# CAS_4.net
KiCad netlist of a schematic drawn in Altium Designer
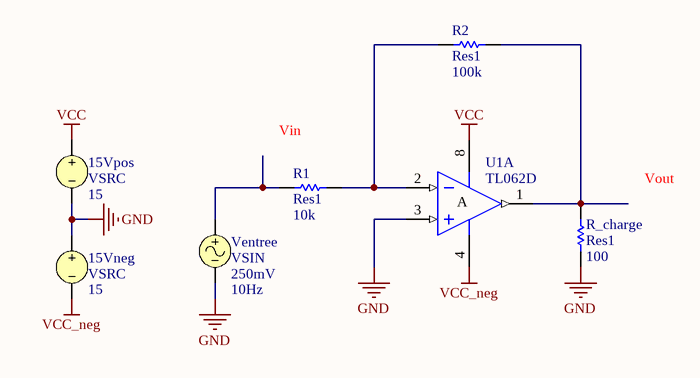
[diagram p0: CAS_4.SchDoc]

(export (version "E")
  (design (tool "Eeschema 10.0.6"))
  (components
    (comp (ref "15Vneg")
      (value "VSRC")
      (description "Voltage Source")
      (fields (field (name "ALTIUM_VALUE") "15") (field (name "PUBLISHER") "Altium Limited"))
      (libsource (lib "Simulation Generic Components") (part "VSRC"))
    )
    (comp (ref "15Vpos")
      (value "VSRC")
      (description "Voltage Source")
      (fields (field (name "ALTIUM_VALUE") "15") (field (name "PUBLISHER") "Altium Limited"))
      (libsource (lib "Simulation Generic Components") (part "VSRC"))
    )
    (comp (ref "R1")
      (value "Res1")
      (footprint "AXIAL-0.3")
      (description "Resistor")
      (fields (field (name "ALTIUM_VALUE") "10k") (field (name "PUBLISHER") "Altium Limited"))
      (libsource (lib "Miscellaneous Devices") (part "Res1"))
    )
    (comp (ref "R2")
      (value "Res1")
      (footprint "AXIAL-0.3")
      (description "Resistor")
      (fields (field (name "ALTIUM_VALUE") "100k") (field (name "PUBLISHER") "Altium Limited"))
      (libsource (lib "Miscellaneous Devices") (part "Res1"))
    )
    (comp (ref "R_charge")
      (value "Res1")
      (footprint "AXIAL-0.3")
      (description "Resistor")
      (fields (field (name "ALTIUM_VALUE") "100") (field (name "PUBLISHER") "Altium Limited"))
      (libsource (lib "Miscellaneous Devices") (part "Res1"))
    )
    (comp (ref "U1")
      (value "TL062D")
      (footprint "D008_L")
      (description "Low-Power JFET-Input Operational Amplifier")
      (fields (field (name "PUBLISHER") "Altium Limited"))
      (libsource (lib "TI Operational Amplifier") (part "TL062D"))
    )
    (comp (ref "Ventree")
      (value "VSIN")
      (description "Sinusoidal Voltage Source")
      (fields
        (field (name "AMPLITUDE") "250mV")
        (field (name "FREQUENCY") "10Hz")
        (field (name "PUBLISHER") "Altium Limited")
      )
      (libsource (lib "Simulation Sources") (part "VSIN"))
    )
  )
  (nets
    (net (code "1") (name "GND") (class "Default")
      (node (ref "15Vneg") (pin "1") (pinfunction "1_1") (pintype "passive"))
      (node (ref "15Vpos") (pin "2") (pinfunction "2_2") (pintype "passive"))
      (node (ref "R_charge") (pin "1") (pinfunction "1_1") (pintype "passive"))
      (node (ref "U1") (pin "3") (pinfunction "IN+_3") (pintype "input"))
      (node (ref "Ventree") (pin "2") (pinfunction "2_2") (pintype "passive"))
    )
    (net (code "2") (name "Net-(R1-Pad1)") (class "Default")
      (node (ref "R1") (pin "1") (pinfunction "1_1") (pintype "passive"))
      (node (ref "Ventree") (pin "1") (pinfunction "1_1") (pintype "passive"))
    )
    (net (code "3") (name "Net-(U1A-IN-)") (class "Default")
      (node (ref "R1") (pin "2") (pinfunction "2_2") (pintype "passive"))
      (node (ref "R2") (pin "1") (pinfunction "1_1") (pintype "passive"))
      (node (ref "U1") (pin "2") (pinfunction "IN-_2") (pintype "input"))
    )
    (net (code "4") (name "Net-(U1A-OUT)") (class "Default")
      (node (ref "R2") (pin "2") (pinfunction "2_2") (pintype "passive"))
      (node (ref "R_charge") (pin "2") (pinfunction "2_2") (pintype "passive"))
      (node (ref "U1") (pin "1") (pinfunction "OUT_1") (pintype "output"))
    )
    (net (code "5") (name "VCC") (class "Default")
      (node (ref "15Vpos") (pin "1") (pinfunction "1_1") (pintype "passive"))
      (node (ref "U1") (pin "8") (pinfunction "V+_8") (pintype "power_in"))
    )
    (net (code "6") (name "VCC_neg") (class "Default")
      (node (ref "15Vneg") (pin "2") (pinfunction "2_2") (pintype "passive"))
      (node (ref "U1") (pin "4") (pinfunction "V-_4") (pintype "power_in"))
    )
  )
)
